# 14_-_JLINK_Debugger.net
KiCad netlist of a schematic drawn in Altium Designer
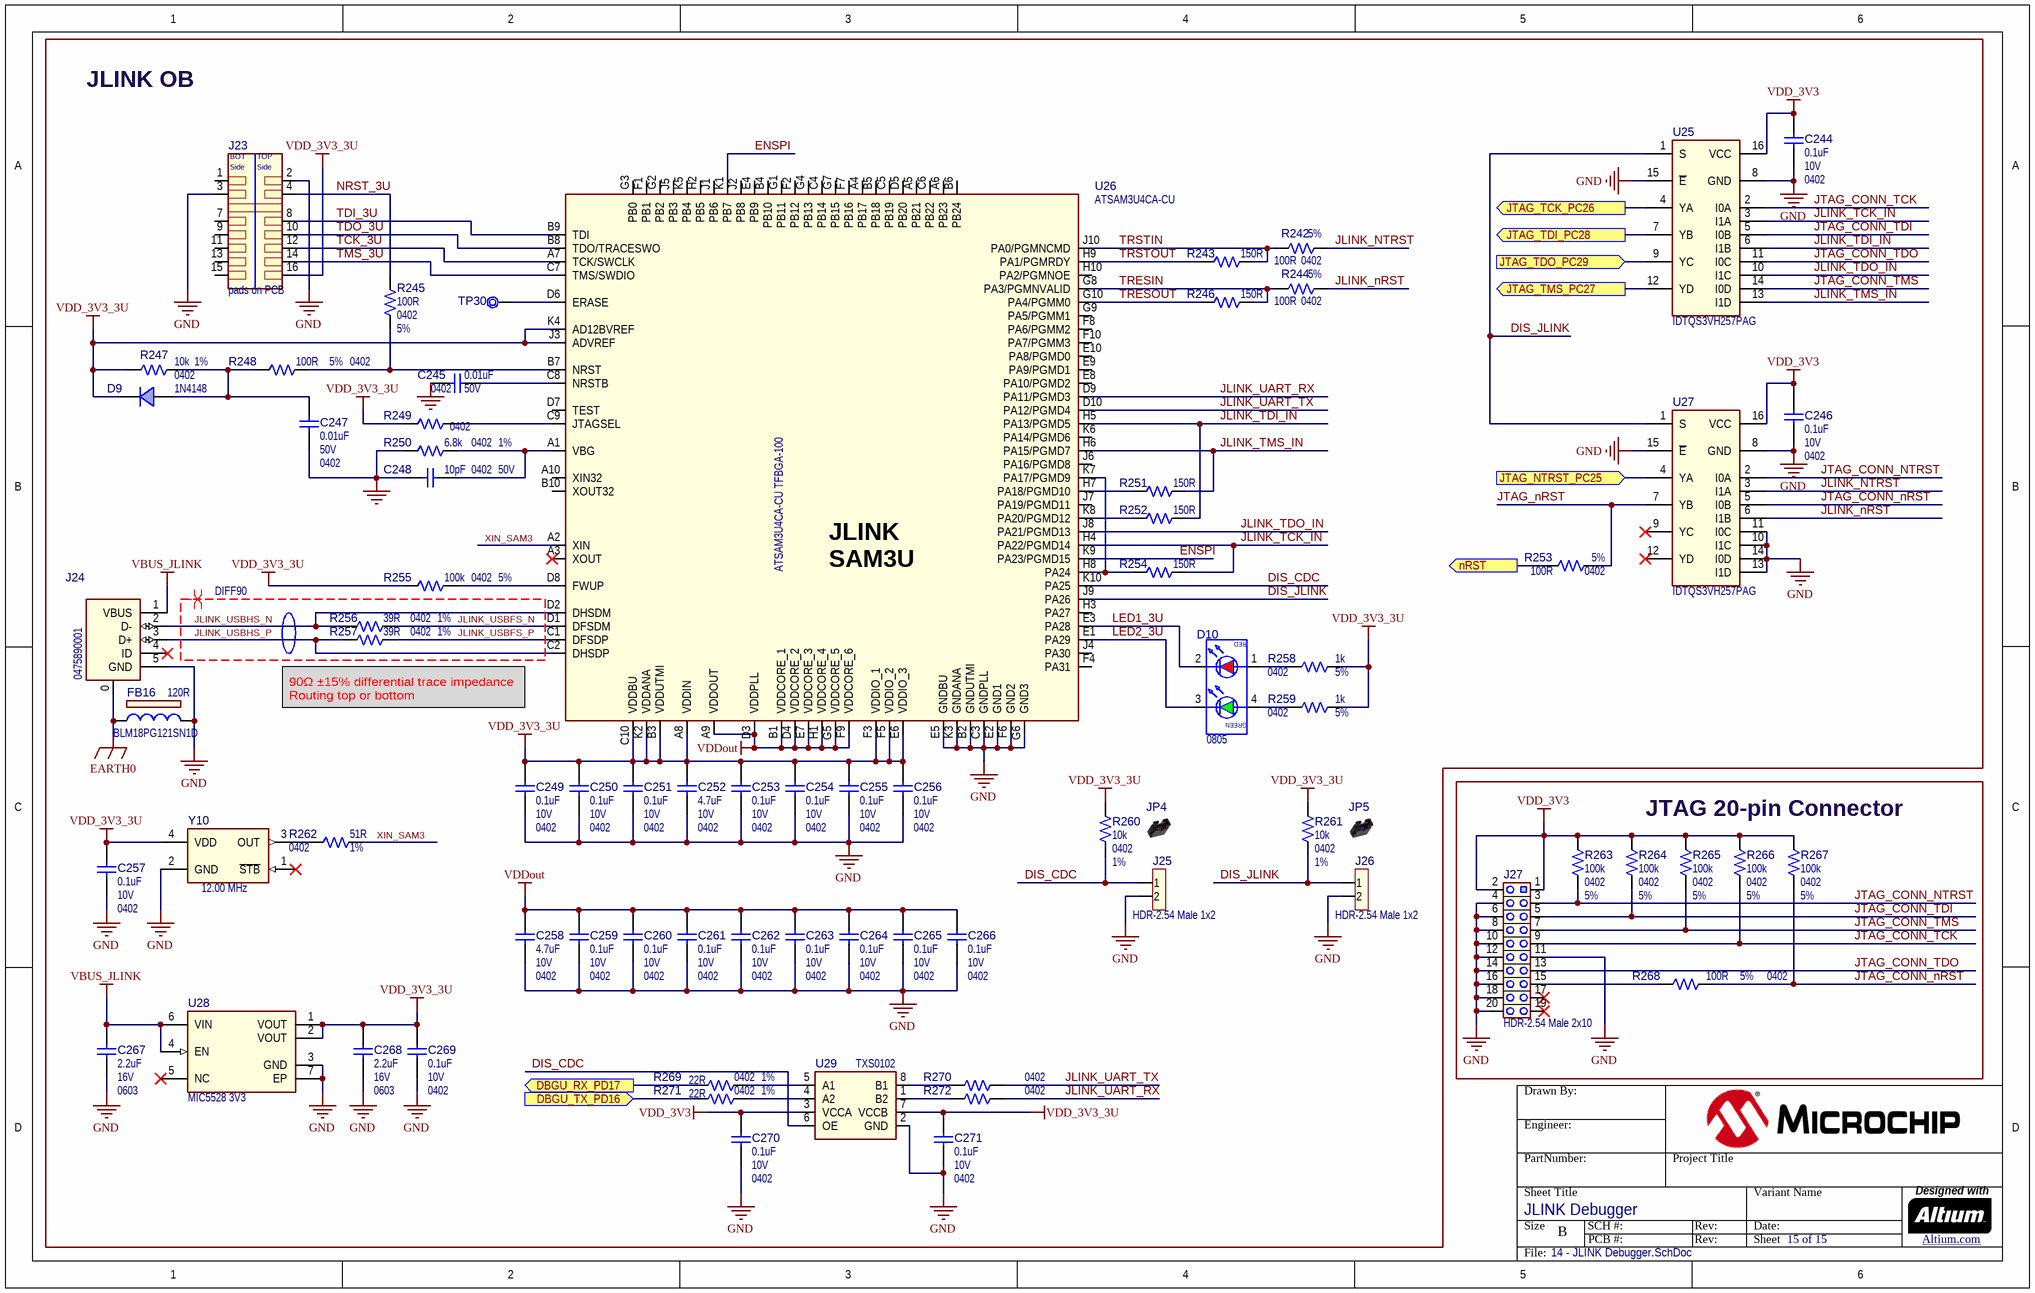
[diagram p0: 14 - JLINK Debugger.SchDoc]

(export (version "E")
  (design (tool "Eeschema 10.0.6"))
  (components
    (comp (ref "C244")
      (value "0.1uF")
      (footprint "CAP_C_0402")
      (description "Capacitor")
      (fields
        (field (name "VOLTAGE") "10V")
        (field (name "PACKAGE") "0402")
        (field (name "TOLERANCE") "10%")
        (field (name "Comment") "Capacitor NP")
      )
      (libsource (lib "MCHP-CDB") (part "Capacitor NP"))
    )
    (comp (ref "C245")
      (value "0.01uF")
      (footprint "CAP_C_0402")
      (description "Capacitor")
      (fields
        (field (name "VOLTAGE") "50V")
        (field (name "PACKAGE") "0402")
        (field (name "TOLERANCE") "10%")
        (field (name "Comment") "Capacitor NP")
      )
      (libsource (lib "MCHP-CDB") (part "Capacitor NP"))
    )
    (comp (ref "C246")
      (value "0.1uF")
      (footprint "CAP_C_0402")
      (description "Capacitor")
      (fields
        (field (name "VOLTAGE") "10V")
        (field (name "PACKAGE") "0402")
        (field (name "TOLERANCE") "10%")
        (field (name "Comment") "Capacitor NP")
      )
      (libsource (lib "MCHP-CDB") (part "Capacitor NP"))
    )
    (comp (ref "C247")
      (value "0.01uF")
      (footprint "CAP_C_0402")
      (description "Capacitor")
      (fields
        (field (name "VOLTAGE") "50V")
        (field (name "PACKAGE") "0402")
        (field (name "TOLERANCE") "10%")
        (field (name "Comment") "Capacitor NP")
      )
      (libsource (lib "MCHP-CDB") (part "Capacitor NP"))
    )
    (comp (ref "C248")
      (value "10pF")
      (footprint "CAP_C_0402")
      (fields
        (field (name "VOLTAGE") "50V")
        (field (name "PACKAGE") "0402")
        (field (name "TOLERANCE") "5%")
        (field (name "Comment") "Capacitor NP")
      )
      (libsource (lib "") (part "Capacitor NP_1"))
    )
    (comp (ref "C249")
      (value "0.1uF")
      (footprint "CAP_C_0402")
      (description "Capacitor")
      (fields
        (field (name "VOLTAGE") "10V")
        (field (name "PACKAGE") "0402")
        (field (name "TOLERANCE") "10%")
        (field (name "Comment") "Capacitor NP")
      )
      (libsource (lib "MCHP-CDB") (part "Capacitor NP"))
    )
    (comp (ref "C250")
      (value "0.1uF")
      (footprint "CAP_C_0402")
      (description "Capacitor")
      (fields
        (field (name "VOLTAGE") "10V")
        (field (name "PACKAGE") "0402")
        (field (name "TOLERANCE") "10%")
        (field (name "Comment") "Capacitor NP")
      )
      (libsource (lib "MCHP-CDB") (part "Capacitor NP"))
    )
    (comp (ref "C251")
      (value "0.1uF")
      (footprint "CAP_C_0402")
      (description "Capacitor")
      (fields
        (field (name "VOLTAGE") "10V")
        (field (name "PACKAGE") "0402")
        (field (name "TOLERANCE") "10%")
        (field (name "Comment") "Capacitor NP")
      )
      (libsource (lib "MCHP-CDB") (part "Capacitor NP"))
    )
    (comp (ref "C252")
      (value "4.7uF")
      (footprint "CAP_C_0402")
      (description "Capacitor")
      (fields
        (field (name "VOLTAGE") "10V")
        (field (name "PACKAGE") "0402")
        (field (name "TOLERANCE") "10%")
        (field (name "Comment") "Capacitor NP")
      )
      (libsource (lib "MCHP-CDB") (part "Capacitor NP"))
    )
    (comp (ref "C253")
      (value "0.1uF")
      (footprint "CAP_C_0402")
      (description "Capacitor")
      (fields
        (field (name "VOLTAGE") "10V")
        (field (name "PACKAGE") "0402")
        (field (name "TOLERANCE") "10%")
        (field (name "Comment") "Capacitor NP")
      )
      (libsource (lib "MCHP-CDB") (part "Capacitor NP"))
    )
    (comp (ref "C254")
      (value "0.1uF")
      (footprint "CAP_C_0402")
      (description "Capacitor")
      (fields
        (field (name "VOLTAGE") "10V")
        (field (name "PACKAGE") "0402")
        (field (name "TOLERANCE") "10%")
        (field (name "Comment") "Capacitor NP")
      )
      (libsource (lib "MCHP-CDB") (part "Capacitor NP"))
    )
    (comp (ref "C255")
      (value "0.1uF")
      (footprint "CAP_C_0402")
      (description "Capacitor")
      (fields
        (field (name "VOLTAGE") "10V")
        (field (name "PACKAGE") "0402")
        (field (name "TOLERANCE") "10%")
        (field (name "Comment") "Capacitor NP")
      )
      (libsource (lib "MCHP-CDB") (part "Capacitor NP"))
    )
    (comp (ref "C256")
      (value "0.1uF")
      (footprint "CAP_C_0402")
      (description "Capacitor")
      (fields
        (field (name "VOLTAGE") "10V")
        (field (name "PACKAGE") "0402")
        (field (name "TOLERANCE") "10%")
        (field (name "Comment") "Capacitor NP")
      )
      (libsource (lib "MCHP-CDB") (part "Capacitor NP"))
    )
    (comp (ref "C257")
      (value "0.1uF")
      (footprint "CAP_C_0402")
      (description "Capacitor")
      (fields
        (field (name "VOLTAGE") "10V")
        (field (name "PACKAGE") "0402")
        (field (name "TOLERANCE") "10%")
        (field (name "Comment") "Capacitor NP")
      )
      (libsource (lib "MCHP-CDB") (part "Capacitor NP"))
    )
    (comp (ref "C258")
      (value "4.7uF")
      (footprint "CAP_C_0402")
      (description "Capacitor")
      (fields
        (field (name "VOLTAGE") "10V")
        (field (name "PACKAGE") "0402")
        (field (name "TOLERANCE") "10%")
        (field (name "Comment") "Capacitor NP")
      )
      (libsource (lib "MCHP-CDB") (part "Capacitor NP"))
    )
    (comp (ref "C259")
      (value "0.1uF")
      (footprint "CAP_C_0402")
      (description "Capacitor")
      (fields
        (field (name "VOLTAGE") "10V")
        (field (name "PACKAGE") "0402")
        (field (name "TOLERANCE") "10%")
        (field (name "Comment") "Capacitor NP")
      )
      (libsource (lib "MCHP-CDB") (part "Capacitor NP"))
    )
    (comp (ref "C260")
      (value "0.1uF")
      (footprint "CAP_C_0402")
      (description "Capacitor")
      (fields
        (field (name "VOLTAGE") "10V")
        (field (name "PACKAGE") "0402")
        (field (name "TOLERANCE") "10%")
        (field (name "Comment") "Capacitor NP")
      )
      (libsource (lib "MCHP-CDB") (part "Capacitor NP"))
    )
    (comp (ref "C261")
      (value "0.1uF")
      (footprint "CAP_C_0402")
      (description "Capacitor")
      (fields
        (field (name "VOLTAGE") "10V")
        (field (name "PACKAGE") "0402")
        (field (name "TOLERANCE") "10%")
        (field (name "Comment") "Capacitor NP")
      )
      (libsource (lib "MCHP-CDB") (part "Capacitor NP"))
    )
    (comp (ref "C262")
      (value "0.1uF")
      (footprint "CAP_C_0402")
      (description "Capacitor")
      (fields
        (field (name "VOLTAGE") "10V")
        (field (name "PACKAGE") "0402")
        (field (name "TOLERANCE") "10%")
        (field (name "Comment") "Capacitor NP")
      )
      (libsource (lib "MCHP-CDB") (part "Capacitor NP"))
    )
    (comp (ref "C263")
      (value "0.1uF")
      (footprint "CAP_C_0402")
      (description "Capacitor")
      (fields
        (field (name "VOLTAGE") "10V")
        (field (name "PACKAGE") "0402")
        (field (name "TOLERANCE") "10%")
        (field (name "Comment") "Capacitor NP")
      )
      (libsource (lib "MCHP-CDB") (part "Capacitor NP"))
    )
    (comp (ref "C264")
      (value "0.1uF")
      (footprint "CAP_C_0402")
      (description "Capacitor")
      (fields
        (field (name "VOLTAGE") "10V")
        (field (name "PACKAGE") "0402")
        (field (name "TOLERANCE") "10%")
        (field (name "Comment") "Capacitor NP")
      )
      (libsource (lib "MCHP-CDB") (part "Capacitor NP"))
    )
    (comp (ref "C265")
      (value "0.1uF")
      (footprint "CAP_C_0402")
      (description "Capacitor")
      (fields
        (field (name "VOLTAGE") "10V")
        (field (name "PACKAGE") "0402")
        (field (name "TOLERANCE") "10%")
        (field (name "Comment") "Capacitor NP")
      )
      (libsource (lib "MCHP-CDB") (part "Capacitor NP"))
    )
    (comp (ref "C266")
      (value "0.1uF")
      (footprint "CAP_C_0402")
      (description "Capacitor")
      (fields
        (field (name "VOLTAGE") "10V")
        (field (name "PACKAGE") "0402")
        (field (name "TOLERANCE") "10%")
        (field (name "Comment") "Capacitor NP")
      )
      (libsource (lib "MCHP-CDB") (part "Capacitor NP"))
    )
    (comp (ref "C267")
      (value "2.2uF")
      (footprint "CAP_C_0603")
      (description "Capacitor")
      (fields
        (field (name "VOLTAGE") "16V")
        (field (name "PACKAGE") "0603")
        (field (name "TOLERANCE") "10%")
        (field (name "Comment") "Capacitor NP")
      )
      (libsource (lib "MCHP-CDB") (part "Capacitor NP"))
    )
    (comp (ref "C268")
      (value "2.2uF")
      (footprint "CAP_C_0603")
      (description "Capacitor")
      (fields
        (field (name "VOLTAGE") "16V")
        (field (name "PACKAGE") "0603")
        (field (name "TOLERANCE") "10%")
        (field (name "Comment") "Capacitor NP")
      )
      (libsource (lib "MCHP-CDB") (part "Capacitor NP"))
    )
    (comp (ref "C269")
      (value "0.1uF")
      (footprint "CAP_C_0402")
      (description "Capacitor")
      (fields
        (field (name "VOLTAGE") "10V")
        (field (name "PACKAGE") "0402")
        (field (name "TOLERANCE") "10%")
        (field (name "Comment") "Capacitor NP")
      )
      (libsource (lib "MCHP-CDB") (part "Capacitor NP"))
    )
    (comp (ref "C270")
      (value "0.1uF")
      (footprint "CAP_C_0402")
      (description "Capacitor")
      (fields
        (field (name "VOLTAGE") "10V")
        (field (name "PACKAGE") "0402")
        (field (name "TOLERANCE") "10%")
        (field (name "Comment") "Capacitor NP")
      )
      (libsource (lib "MCHP-CDB") (part "Capacitor NP"))
    )
    (comp (ref "C271")
      (value "0.1uF")
      (footprint "CAP_C_0402")
      (description "Capacitor")
      (fields
        (field (name "VOLTAGE") "10V")
        (field (name "PACKAGE") "0402")
        (field (name "TOLERANCE") "10%")
        (field (name "Comment") "Capacitor NP")
      )
      (libsource (lib "MCHP-CDB") (part "Capacitor NP"))
    )
    (comp (ref "D9")
      (value "1N4148")
      (footprint "SOD-323")
      (description "DIO RECT 1N4148 855mV 300mA 75V SOD-323")
      (fields (field (name "POWER") "200mW") (field (name "Comment") "Diode Single"))
      (libsource (lib "MCHP-CDB") (part "Diode Single"))
    )
    (comp (ref "D10")
      (value "LED DUAL 4 pin")
      (footprint "LED_DUAL_SMD_2x1.25mm")
      (description "LED")
      (fields (field (name "PACKAGE") "0805") (field (name "POWER") "75mW"))
      (libsource (lib "MCHP-CDB") (part "LED DUAL 4 pin"))
    )
    (comp (ref "FB16")
      (value "120R")
      (footprint "IND_C_0603")
      (fields
        (field (name "MANUFACTURER PART NUMBER 1") "BLM18PG121SN1D")
        (field (name "Comment") "Ferrite Bead")
      )
      (libsource (lib "MCHP-CDB") (part "Ferrite Bead"))
    )
    (comp (ref "J23")
      (value "pads on PCB")
      (footprint "CON_EDGE-CARD_PCB_RA_MEC1-108-02-F-D-RA1-SL")
      (description "CON_PCB_MEC1-108-02-F-D-RA1-SL")
      (libsource (lib "MCHP-CDB") (part "CON_PCB_MEC1-108-02-F-D-RA1-SL"))
    )
    (comp (ref "J24")
      (value "0475890001")
      (footprint "CON_USB_Micro-AB_SMD_RA_MOLEX_0475890001")
      (fields (field (name "VOLTAGE") "30VAC") (field (name "Comment") "CON USB2.0 Mini_Micro"))
      (libsource (lib "MCHP-CDB") (part "CON USB2.0 Mini_Micro"))
    )
    (comp (ref "J25")
      (value "HDR-2.54 Male 1x2")
      (footprint "HDR_M_2.54_1x2")
      (fields (field (name "Comment") "Header 1x2"))
      (libsource (lib "MCHP-CDB") (part "Header 1x2"))
    )
    (comp (ref "J26")
      (value "HDR-2.54 Male 1x2")
      (footprint "HDR_M_2.54_1x2")
      (fields (field (name "Comment") "Header 1x2"))
      (libsource (lib "MCHP-CDB") (part "Header 1x2"))
    )
    (comp (ref "J27")
      (value "HDR-2.54 Male 2x10")
      (footprint "HDR_M_2.54_2X10_S_TH_V_SAM_TST-110-01-G-D")
      (fields (field (name "Comment") "Header 2x10"))
      (libsource (lib "MCHP-CDB") (part "Header 2x10"))
    )
    (comp (ref "JP4")
      (value "Jumper Mechanical")
      (footprint "Jumper_Mechanical")
      (libsource (lib "MCHP-CDB") (part "Jumper Mechanical"))
    )
    (comp (ref "JP5")
      (value "Jumper Mechanical")
      (footprint "Jumper_Mechanical")
      (libsource (lib "MCHP-CDB") (part "Jumper Mechanical"))
    )
    (comp (ref "R242")
      (value "100R")
      (footprint "RES_C_0402")
      (description "Resistor")
      (fields
        (field (name "PACKAGE") "0402")
        (field (name "TOLERANCE") "5%")
        (field (name "VOLTAGE") "50V")
        (field (name "POWER") "1/16W")
      )
      (libsource (lib "MCHP-CDB") (part "Resistor"))
    )
    (comp (ref "R243")
      (value "150R")
      (footprint "RES_C_0402")
      (description "Resistor")
      (libsource (lib "MCHP-CDB") (part "Resistor"))
    )
    (comp (ref "R244")
      (value "100R")
      (footprint "RES_C_0402")
      (description "Resistor")
      (fields
        (field (name "PACKAGE") "0402")
        (field (name "TOLERANCE") "5%")
        (field (name "VOLTAGE") "50V")
        (field (name "POWER") "1/16W")
      )
      (libsource (lib "MCHP-CDB") (part "Resistor"))
    )
    (comp (ref "R245")
      (value "100R")
      (footprint "RES_C_0402")
      (description "Resistor")
      (fields
        (field (name "PACKAGE") "0402")
        (field (name "TOLERANCE") "5%")
        (field (name "VOLTAGE") "50V")
        (field (name "POWER") "1/16W")
      )
      (libsource (lib "MCHP-CDB") (part "Resistor"))
    )
    (comp (ref "R246")
      (value "150R")
      (footprint "RES_C_0402")
      (description "Resistor")
      (libsource (lib "MCHP-CDB") (part "Resistor"))
    )
    (comp (ref "R247")
      (value "10k")
      (footprint "RES_C_0402")
      (description "Resistor")
      (fields
        (field (name "PACKAGE") "0402")
        (field (name "TOLERANCE") "1%")
        (field (name "VOLTAGE") "50V")
        (field (name "POWER") "1/10W")
      )
      (libsource (lib "MCHP-CDB") (part "Resistor"))
    )
    (comp (ref "R248")
      (value "100R")
      (footprint "RES_C_0402")
      (description "Resistor")
      (fields
        (field (name "PACKAGE") "0402")
        (field (name "TOLERANCE") "5%")
        (field (name "VOLTAGE") "50V")
        (field (name "POWER") "1/16W")
      )
      (libsource (lib "MCHP-CDB") (part "Resistor"))
    )
    (comp (ref "R249")
      (value "Resistor")
      (footprint "RES_C_0402")
      (fields (field (name "PACKAGE") "0402") (field (name "POWER") "1/16W") (field (name "VOLTAGE") "50V"))
      (libsource (lib "MCHP-CDB") (part "Resistor"))
    )
    (comp (ref "R250")
      (value "6.8k")
      (footprint "RES_C_0402")
      (description "Resistor")
      (fields
        (field (name "PACKAGE") "0402")
        (field (name "TOLERANCE") "1%")
        (field (name "VOLTAGE") "50V")
        (field (name "POWER") "1/16W")
      )
      (libsource (lib "MCHP-CDB") (part "Resistor"))
    )
    (comp (ref "R251")
      (value "150R")
      (footprint "RES_C_0402")
      (description "Resistor")
      (libsource (lib "MCHP-CDB") (part "Resistor"))
    )
    (comp (ref "R252")
      (value "150R")
      (footprint "RES_C_0402")
      (description "Resistor")
      (libsource (lib "MCHP-CDB") (part "Resistor"))
    )
    (comp (ref "R253")
      (value "100R")
      (footprint "RES_C_0402")
      (description "Resistor")
      (fields
        (field (name "PACKAGE") "0402")
        (field (name "TOLERANCE") "5%")
        (field (name "VOLTAGE") "50V")
        (field (name "POWER") "1/16W")
      )
      (libsource (lib "MCHP-CDB") (part "Resistor"))
    )
    (comp (ref "R254")
      (value "150R")
      (footprint "RES_C_0402")
      (description "Resistor")
      (libsource (lib "MCHP-CDB") (part "Resistor"))
    )
    (comp (ref "R255")
      (value "100k")
      (footprint "RES_C_0402")
      (description "Resistor")
      (fields
        (field (name "PACKAGE") "0402")
        (field (name "TOLERANCE") "5%")
        (field (name "POWER") "1/10W")
        (field (name "VOLTAGE") "50V")
      )
      (libsource (lib "MCHP-CDB") (part "Resistor"))
    )
    (comp (ref "R256")
      (value "39R")
      (footprint "RES_C_0402")
      (description "Resistor")
      (fields
        (field (name "PACKAGE") "0402")
        (field (name "TOLERANCE") "1%")
        (field (name "POWER") "1/16W")
        (field (name "VOLTAGE") "50V")
      )
      (libsource (lib "MCHP-CDB") (part "Resistor"))
    )
    (comp (ref "R257")
      (value "39R")
      (footprint "RES_C_0402")
      (description "Resistor")
      (fields
        (field (name "PACKAGE") "0402")
        (field (name "TOLERANCE") "1%")
        (field (name "POWER") "1/16W")
        (field (name "VOLTAGE") "50V")
      )
      (libsource (lib "MCHP-CDB") (part "Resistor"))
    )
    (comp (ref "R258")
      (value "1k")
      (footprint "RES_C_0402")
      (description "Resistor")
      (fields
        (field (name "PACKAGE") "0402")
        (field (name "TOLERANCE") "5%")
        (field (name "VOLTAGE") "50V")
        (field (name "POWER") "1/16W")
      )
      (libsource (lib "MCHP-CDB") (part "Resistor"))
    )
    (comp (ref "R259")
      (value "1k")
      (footprint "RES_C_0402")
      (description "Resistor")
      (fields
        (field (name "PACKAGE") "0402")
        (field (name "TOLERANCE") "5%")
        (field (name "VOLTAGE") "50V")
        (field (name "POWER") "1/16W")
      )
      (libsource (lib "MCHP-CDB") (part "Resistor"))
    )
    (comp (ref "R260")
      (value "10k")
      (footprint "RES_C_0402")
      (description "Resistor")
      (fields
        (field (name "PACKAGE") "0402")
        (field (name "TOLERANCE") "1%")
        (field (name "VOLTAGE") "50V")
        (field (name "POWER") "1/10W")
      )
      (libsource (lib "MCHP-CDB") (part "Resistor"))
    )
    (comp (ref "R261")
      (value "10k")
      (footprint "RES_C_0402")
      (description "Resistor")
      (fields
        (field (name "PACKAGE") "0402")
        (field (name "TOLERANCE") "1%")
        (field (name "VOLTAGE") "50V")
        (field (name "POWER") "1/10W")
      )
      (libsource (lib "MCHP-CDB") (part "Resistor"))
    )
    (comp (ref "R262")
      (value "51R")
      (footprint "RES_C_0402")
      (description "Resistor")
      (fields
        (field (name "PACKAGE") "0402")
        (field (name "TOLERANCE") "1%")
        (field (name "VOLTAGE") "50V")
        (field (name "POWER") "1/5W")
      )
      (libsource (lib "MCHP-CDB") (part "Resistor"))
    )
    (comp (ref "R263")
      (value "100k")
      (footprint "RES_C_0402")
      (description "Resistor")
      (fields
        (field (name "PACKAGE") "0402")
        (field (name "TOLERANCE") "5%")
        (field (name "POWER") "1/10W")
        (field (name "VOLTAGE") "50V")
      )
      (libsource (lib "MCHP-CDB") (part "Resistor"))
    )
    (comp (ref "R264")
      (value "100k")
      (footprint "RES_C_0402")
      (description "Resistor")
      (fields
        (field (name "PACKAGE") "0402")
        (field (name "TOLERANCE") "5%")
        (field (name "POWER") "1/10W")
        (field (name "VOLTAGE") "50V")
      )
      (libsource (lib "MCHP-CDB") (part "Resistor"))
    )
    (comp (ref "R265")
      (value "100k")
      (footprint "RES_C_0402")
      (description "Resistor")
      (fields
        (field (name "PACKAGE") "0402")
        (field (name "TOLERANCE") "5%")
        (field (name "POWER") "1/10W")
        (field (name "VOLTAGE") "50V")
      )
      (libsource (lib "MCHP-CDB") (part "Resistor"))
    )
    (comp (ref "R266")
      (value "100k")
      (footprint "RES_C_0402")
      (description "Resistor")
      (fields
        (field (name "PACKAGE") "0402")
        (field (name "TOLERANCE") "5%")
        (field (name "POWER") "1/10W")
        (field (name "VOLTAGE") "50V")
      )
      (libsource (lib "MCHP-CDB") (part "Resistor"))
    )
    (comp (ref "R267")
      (value "100k")
      (footprint "RES_C_0402")
      (description "Resistor")
      (fields
        (field (name "PACKAGE") "0402")
        (field (name "TOLERANCE") "5%")
        (field (name "POWER") "1/10W")
        (field (name "VOLTAGE") "50V")
      )
      (libsource (lib "MCHP-CDB") (part "Resistor"))
    )
    (comp (ref "R268")
      (value "100R")
      (footprint "RES_C_0402")
      (description "Resistor")
      (fields
        (field (name "PACKAGE") "0402")
        (field (name "TOLERANCE") "5%")
        (field (name "VOLTAGE") "50V")
        (field (name "POWER") "1/16W")
      )
      (libsource (lib "MCHP-CDB") (part "Resistor"))
    )
    (comp (ref "R269")
      (value "22R")
      (footprint "RES_C_0402")
      (description "Resistor")
      (fields (field (name "PACKAGE") "0402") (field (name "TOLERANCE") "1%") (field (name "POWER") "1/10W"))
      (libsource (lib "MCHP-CDB") (part "Resistor"))
    )
    (comp (ref "R270")
      (value "Resistor")
      (footprint "RES_C_0402")
      (fields (field (name "PACKAGE") "0402") (field (name "POWER") "1/16W") (field (name "VOLTAGE") "50V"))
      (libsource (lib "MCHP-CDB") (part "Resistor"))
    )
    (comp (ref "R271")
      (value "22R")
      (footprint "RES_C_0402")
      (description "Resistor")
      (fields (field (name "PACKAGE") "0402") (field (name "TOLERANCE") "1%") (field (name "POWER") "1/10W"))
      (libsource (lib "MCHP-CDB") (part "Resistor"))
    )
    (comp (ref "R272")
      (value "Resistor")
      (footprint "RES_C_0402")
      (fields (field (name "PACKAGE") "0402") (field (name "POWER") "1/16W") (field (name "VOLTAGE") "50V"))
      (libsource (lib "MCHP-CDB") (part "Resistor"))
    )
    (comp (ref "TP30")
      (value "Test Point No BOM")
      (footprint "TP_1mm_SMD")
      (description "Test Point")
      (libsource (lib "MCHP-CDB") (part "Test Point No BOM"))
    )
    (comp (ref "U25")
      (value "IDTQS3VH257PAG")
      (footprint "TSSOP-16")
      (fields (field (name "Comment") "IDTQS3VH257 TSSOP-16"))
      (libsource (lib "MCHP-CDB") (part "IDTQS3VH257 TSSOP-16"))
    )
    (comp (ref "U26")
      (value "ATSAM3U4CA-CU TFBGA-100")
      (footprint "TFBGA-100_P0.8_9x9x1.1")
      (fields (field (name "ALTIUM_VALUE") "ATSAM3U4CA-CU"))
      (libsource (lib "MCHP-CDB") (part "ATSAM3U4CA-CU TFBGA-100"))
    )
    (comp (ref "U27")
      (value "IDTQS3VH257PAG")
      (footprint "TSSOP-16")
      (fields (field (name "Comment") "IDTQS3VH257 TSSOP-16"))
      (libsource (lib "MCHP-CDB") (part "IDTQS3VH257 TSSOP-16"))
    )
    (comp (ref "U28")
      (value "MIC5528 3V3")
      (footprint "DFN-6_1.2x1.2")
      (fields (field (name "Comment") "MIC5528MT DFN-6"))
      (libsource (lib "MCHP-CDB") (part "MIC5528MT DFN-6"))
    )
    (comp (ref "U29")
      (value "TXS0102")
      (footprint "US-8")
      (description "Level Shifter")
      (libsource (lib "MCHP-CDB") (part "TXS0102"))
    )
    (comp (ref "Y10")
      (value "12.00 MHz")
      (footprint "OSCILLATOR_DSC60000L2.5W2.0H0.89")
      (fields (field (name "Comment") "OSCILLATOR DSC60XX"))
      (libsource (lib "MCHP-CDB") (part "OSCILLATOR DSC60XX"))
    )
  )
  (nets
    (net (code "1") (name "/DBGU_RX_PD17") (class "Default")
      (node (ref "R269") (pin "1") (pinfunction "1_1") (pintype "passive"))
    )
    (net (code "2") (name "/DBGU_TX_PD16") (class "Default")
      (node (ref "R271") (pin "1") (pinfunction "1_1") (pintype "passive"))
    )
    (net (code "3") (name "/DIS_CDC") (class "Default")
      (node (ref "J25") (pin "1") (pinfunction "1_1") (pintype "passive"))
      (node (ref "R260") (pin "2") (pinfunction "2_2") (pintype "passive"))
      (node (ref "U26") (pin "K10") (pinfunction "PA25_K10") (pintype "passive"))
      (node (ref "U29") (pin "6") (pinfunction "OE_6") (pintype "passive"))
    )
    (net (code "4") (name "/DIS_JLINK") (class "Default")
      (node (ref "J26") (pin "1") (pinfunction "1_1") (pintype "passive"))
      (node (ref "R261") (pin "2") (pinfunction "2_2") (pintype "passive"))
      (node (ref "U25") (pin "1") (pinfunction "S_1") (pintype "passive"))
      (node (ref "U26") (pin "J9") (pinfunction "PA26_J9") (pintype "passive"))
      (node (ref "U27") (pin "1") (pinfunction "S_1") (pintype "passive"))
    )
    (net (code "5") (name "/ENSPI") (class "Default")
      (node (ref "U26") (pin "K1") (pinfunction "PB7_K1") (pintype "passive"))
      (node (ref "U26") (pin "K9") (pinfunction "PA23/PGMD15_K9") (pintype "passive"))
    )
    (net (code "6") (name "/JLINK_NTRST") (class "Default")
      (node (ref "R242") (pin "2") (pinfunction "2_2") (pintype "passive"))
      (node (ref "U27") (pin "3") (pinfunction "I1A_3") (pintype "passive"))
    )
    (net (code "7") (name "/JLINK_TCK_IN") (class "Default")
      (node (ref "R254") (pin "2") (pinfunction "2_2") (pintype "passive"))
      (node (ref "U25") (pin "3") (pinfunction "I1A_3") (pintype "passive"))
      (node (ref "U26") (pin "H4") (pinfunction "PA22/PGMD14_H4") (pintype "passive"))
    )
    (net (code "8") (name "/JLINK_TDI_IN") (class "Default")
      (node (ref "R252") (pin "2") (pinfunction "2_2") (pintype "passive"))
      (node (ref "U25") (pin "6") (pinfunction "I1B_6") (pintype "passive"))
      (node (ref "U26") (pin "H5") (pinfunction "PA13/PGMD5_H5") (pintype "passive"))
    )
    (net (code "9") (name "/JLINK_TDO_IN") (class "Default")
      (node (ref "U25") (pin "10") (pinfunction "I1C_10") (pintype "passive"))
      (node (ref "U26") (pin "J8") (pinfunction "PA21/PGMD13_J8") (pintype "passive"))
    )
    (net (code "10") (name "/JLINK_TMS_IN") (class "Default")
      (node (ref "R251") (pin "2") (pinfunction "2_2") (pintype "passive"))
      (node (ref "U25") (pin "13") (pinfunction "I1D_13") (pintype "passive"))
      (node (ref "U26") (pin "H6") (pinfunction "PA15/PGMD7_H6") (pintype "passive"))
    )
    (net (code "11") (name "/JLINK_UART_RX") (class "Default")
      (node (ref "R272") (pin "2") (pinfunction "2_2") (pintype "passive"))
      (node (ref "U26") (pin "D9") (pinfunction "PA11/PGMD3_D9") (pintype "passive"))
    )
    (net (code "12") (name "/JLINK_UART_TX") (class "Default")
      (node (ref "R270") (pin "2") (pinfunction "2_2") (pintype "passive"))
      (node (ref "U26") (pin "D10") (pinfunction "PA12/PGMD4_D10") (pintype "passive"))
    )
    (net (code "13") (name "/JLINK_USBFS_N") (class "Default")
      (node (ref "R256") (pin "2") (pinfunction "2_2") (pintype "passive"))
      (node (ref "U26") (pin "D1") (pinfunction "DFSDM_D1") (pintype "passive"))
    )
    (net (code "14") (name "/JLINK_USBFS_P") (class "Default")
      (node (ref "R257") (pin "2") (pinfunction "2_2") (pintype "passive"))
      (node (ref "U26") (pin "C1") (pinfunction "DFSDP_C1") (pintype "passive"))
    )
    (net (code "15") (name "/JLINK_USBHS_N") (class "Default")
      (node (ref "J24") (pin "2") (pinfunction "D-_2") (pintype "bidirectional"))
      (node (ref "R256") (pin "1") (pinfunction "1_1") (pintype "passive"))
      (node (ref "U26") (pin "D2") (pinfunction "DHSDM_D2") (pintype "passive"))
    )
    (net (code "16") (name "/JLINK_USBHS_P") (class "Default")
      (node (ref "J24") (pin "3") (pinfunction "D+_3") (pintype "bidirectional"))
      (node (ref "R257") (pin "1") (pinfunction "1_1") (pintype "passive"))
      (node (ref "U26") (pin "C2") (pinfunction "DHSDP_C2") (pintype "passive"))
    )
    (net (code "17") (name "/JLINK_nRST") (class "Default")
      (node (ref "R244") (pin "2") (pinfunction "2_2") (pintype "passive"))
      (node (ref "U27") (pin "6") (pinfunction "I1B_6") (pintype "passive"))
    )
    (net (code "18") (name "/JTAG_CONN_NTRST") (class "Default")
      (node (ref "J27") (pin "3") (pinfunction "3_3") (pintype "passive"))
      (node (ref "R263") (pin "1") (pinfunction "1_1") (pintype "passive"))
      (node (ref "U27") (pin "2") (pinfunction "I0A_2") (pintype "passive"))
    )
    (net (code "19") (name "/JTAG_CONN_TCK") (class "Default")
      (node (ref "J27") (pin "9") (pinfunction "9_9") (pintype "passive"))
      (node (ref "R266") (pin "2") (pinfunction "2_2") (pintype "passive"))
      (node (ref "U25") (pin "2") (pinfunction "I0A_2") (pintype "passive"))
    )
    (net (code "20") (name "/JTAG_CONN_TDI") (class "Default")
      (node (ref "J27") (pin "5") (pinfunction "5_5") (pintype "passive"))
      (node (ref "R264") (pin "1") (pinfunction "1_1") (pintype "passive"))
      (node (ref "U25") (pin "5") (pinfunction "I0B_5") (pintype "passive"))
    )
    (net (code "21") (name "/JTAG_CONN_TDO") (class "Default")
      (node (ref "J27") (pin "13") (pinfunction "13_13") (pintype "passive"))
      (node (ref "U25") (pin "11") (pinfunction "I0C_11") (pintype "passive"))
    )
    (net (code "22") (name "/JTAG_CONN_TMS") (class "Default")
      (node (ref "J27") (pin "7") (pinfunction "7_7") (pintype "passive"))
      (node (ref "R265") (pin "1") (pinfunction "1_1") (pintype "passive"))
      (node (ref "U25") (pin "14") (pinfunction "I0D_14") (pintype "passive"))
    )
    (net (code "23") (name "/JTAG_CONN_nRST") (class "Default")
      (node (ref "R267") (pin "1") (pinfunction "1_1") (pintype "passive"))
      (node (ref "R268") (pin "1") (pinfunction "1_1") (pintype "passive"))
      (node (ref "U27") (pin "5") (pinfunction "I0B_5") (pintype "passive"))
    )
    (net (code "24") (name "/JTAG_NTRST_PC25") (class "Default")
      (node (ref "U27") (pin "4") (pinfunction "YA_4") (pintype "passive"))
    )
    (net (code "25") (name "/JTAG_TCK_PC26") (class "Default")
      (node (ref "U25") (pin "4") (pinfunction "YA_4") (pintype "passive"))
    )
    (net (code "26") (name "/JTAG_TDI_PC28") (class "Default")
      (node (ref "U25") (pin "7") (pinfunction "YB_7") (pintype "passive"))
    )
    (net (code "27") (name "/JTAG_TDO_PC29") (class "Default")
      (node (ref "U25") (pin "9") (pinfunction "YC_9") (pintype "passive"))
    )
    (net (code "28") (name "/JTAG_TMS_PC27") (class "Default")
      (node (ref "U25") (pin "12") (pinfunction "YD_12") (pintype "passive"))
    )
    (net (code "29") (name "/JTAG_nRST") (class "Default")
      (node (ref "R253") (pin "2") (pinfunction "2_2") (pintype "passive"))
      (node (ref "U27") (pin "7") (pinfunction "YB_7") (pintype "passive"))
    )
    (net (code "30") (name "/LED1_3U") (class "Default")
      (node (ref "D10") (pin "2") (pinfunction "K1_2") (pintype "passive"))
      (node (ref "U26") (pin "E3") (pinfunction "PA28_E3") (pintype "passive"))
    )
    (net (code "31") (name "/LED2_3U") (class "Default")
      (node (ref "D10") (pin "3") (pinfunction "K2_3") (pintype "passive"))
      (node (ref "U26") (pin "E1") (pinfunction "PA29_E1") (pintype "passive"))
    )
    (net (code "32") (name "/NRST_3U") (class "Default")
      (node (ref "J23") (pin "4") (pinfunction "4_4") (pintype "passive"))
      (node (ref "R245") (pin "2") (pinfunction "2_2") (pintype "passive"))
    )
    (net (code "33") (name "/TCK_3U") (class "Default")
      (node (ref "J23") (pin "12") (pinfunction "12_12") (pintype "passive"))
      (node (ref "U26") (pin "A7") (pinfunction "TCK/SWCLK_A7") (pintype "passive"))
    )
    (net (code "34") (name "/TDI_3U") (class "Default")
      (node (ref "J23") (pin "8") (pinfunction "8_8") (pintype "passive"))
      (node (ref "U26") (pin "B9") (pinfunction "TDI_B9") (pintype "passive"))
    )
    (net (code "35") (name "/TDO_3U") (class "Default")
      (node (ref "J23") (pin "10") (pinfunction "10_10") (pintype "passive"))
      (node (ref "U26") (pin "B8") (pinfunction "TDO/TRACESWO_B8") (pintype "passive"))
    )
    (net (code "36") (name "/TMS_3U") (class "Default")
      (node (ref "J23") (pin "14") (pinfunction "14_14") (pintype "passive"))
      (node (ref "U26") (pin "C7") (pinfunction "TMS/SWDIO_C7") (pintype "passive"))
    )
    (net (code "37") (name "/TRESIN") (class "Default")
      (node (ref "R244") (pin "1") (pinfunction "1_1") (pintype "passive"))
      (node (ref "R246") (pin "2") (pinfunction "2_2") (pintype "passive"))
      (node (ref "U26") (pin "G8") (pinfunction "PA3/PGMNVALID_G8") (pintype "passive"))
    )
    (net (code "38") (name "/TRESOUT") (class "Default")
      (node (ref "R246") (pin "1") (pinfunction "1_1") (pintype "passive"))
      (node (ref "U26") (pin "G10") (pinfunction "PA4/PGMM0_G10") (pintype "passive"))
    )
    (net (code "39") (name "/TRSTIN") (class "Default")
      (node (ref "R242") (pin "1") (pinfunction "1_1") (pintype "passive"))
      (node (ref "R243") (pin "2") (pinfunction "2_2") (pintype "passive"))
      (node (ref "U26") (pin "J10") (pinfunction "PA0/PGMNCMD_J10") (pintype "passive"))
    )
    (net (code "40") (name "/TRSTOUT") (class "Default")
      (node (ref "R243") (pin "1") (pinfunction "1_1") (pintype "passive"))
      (node (ref "U26") (pin "H9") (pinfunction "PA1/PGMRDY_H9") (pintype "passive"))
    )
    (net (code "41") (name "/XIN_SAM3") (class "Default")
      (node (ref "R262") (pin "2") (pinfunction "2_2") (pintype "passive"))
      (node (ref "U26") (pin "A2") (pinfunction "XIN_A2") (pintype "passive"))
    )
    (net (code "42") (name "/nRST") (class "Default")
      (node (ref "R253") (pin "1") (pinfunction "1_1") (pintype "passive"))
    )
    (net (code "43") (name "EARTH0") (class "Default")
      (node (ref "FB16") (pin "1") (pinfunction "1_1") (pintype "passive"))
      (node (ref "J24") (pin "0") (pinfunction "SHLD_0") (pintype "passive"))
    )
    (net (code "44") (name "GND") (class "Default")
      (node (ref "C244") (pin "2") (pinfunction "2_2") (pintype "passive"))
      (node (ref "C245") (pin "1") (pinfunction "1_1") (pintype "passive"))
      (node (ref "C246") (pin "2") (pinfunction "2_2") (pintype "passive"))
      (node (ref "C247") (pin "1") (pinfunction "1_1") (pintype "passive"))
      (node (ref "C248") (pin "2") (pinfunction "2_2") (pintype "passive"))
      (node (ref "C249") (pin "2") (pinfunction "2_2") (pintype "passive"))
      (node (ref "C250") (pin "1") (pinfunction "1_1") (pintype "passive"))
      (node (ref "C251") (pin "2") (pinfunction "2_2") (pintype "passive"))
      (node (ref "C252") (pin "1") (pinfunction "1_1") (pintype "passive"))
      (node (ref "C253") (pin "1") (pinfunction "1_1") (pintype "passive"))
      (node (ref "C254") (pin "1") (pinfunction "1_1") (pintype "passive"))
      (node (ref "C255") (pin "1") (pinfunction "1_1") (pintype "passive"))
      (node (ref "C256") (pin "1") (pinfunction "1_1") (pintype "passive"))
      (node (ref "C257") (pin "1") (pinfunction "1_1") (pintype "passive"))
      (node (ref "C258") (pin "1") (pinfunction "1_1") (pintype "passive"))
      (node (ref "C259") (pin "1") (pinfunction "1_1") (pintype "passive"))
      (node (ref "C260") (pin "2") (pinfunction "2_2") (pintype "passive"))
      (node (ref "C261") (pin "2") (pinfunction "2_2") (pintype "passive"))
      (node (ref "C262") (pin "2") (pinfunction "2_2") (pintype "passive"))
      (node (ref "C263") (pin "2") (pinfunction "2_2") (pintype "passive"))
      (node (ref "C264") (pin "2") (pinfunction "2_2") (pintype "passive"))
      (node (ref "C265") (pin "2") (pinfunction "2_2") (pintype "passive"))
      (node (ref "C266") (pin "1") (pinfunction "1_1") (pintype "passive"))
      (node (ref "C267") (pin "2") (pinfunction "2_2") (pintype "passive"))
      (node (ref "C268") (pin "1") (pinfunction "1_1") (pintype "passive"))
      (node (ref "C269") (pin "1") (pinfunction "1_1") (pintype "passive"))
      (node (ref "C270") (pin "1") (pinfunction "1_1") (pintype "passive"))
      (node (ref "C271") (pin "1") (pinfunction "1_1") (pintype "passive"))
      (node (ref "FB16") (pin "2") (pinfunction "2_2") (pintype "passive"))
      (node (ref "J23") (pin "2") (pinfunction "2_2") (pintype "passive"))
      (node (ref "J23") (pin "3") (pinfunction "3_3") (pintype "passive"))
      (node (ref "J24") (pin "5") (pinfunction "GND_5") (pintype "power_in"))
      (node (ref "J25") (pin "2") (pinfunction "2_2") (pintype "passive"))
      (node (ref "J26") (pin "2") (pinfunction "2_2") (pintype "passive"))
      (node (ref "J27") (pin "10") (pinfunction "10_10") (pintype "passive"))
      (node (ref "J27") (pin "11") (pinfunction "11_11") (pintype "passive"))
      (node (ref "J27") (pin "12") (pinfunction "12_12") (pintype "passive"))
      (node (ref "J27") (pin "14") (pinfunction "14_14") (pintype "passive"))
      (node (ref "J27") (pin "16") (pinfunction "16_16") (pintype "passive"))
      (node (ref "J27") (pin "18") (pinfunction "18_18") (pintype "passive"))
      (node (ref "J27") (pin "20") (pinfunction "20_20") (pintype "passive"))
      (node (ref "J27") (pin "4") (pinfunction "4_4") (pintype "passive"))
      (node (ref "J27") (pin "6") (pinfunction "6_6") (pintype "passive"))
      (node (ref "J27") (pin "8") (pinfunction "8_8") (pintype "passive"))
      (node (ref "R250") (pin "1") (pinfunction "1_1") (pintype "passive"))
      (node (ref "U25") (pin "15") (pinfunction "~{E}_15") (pintype "passive"))
      (node (ref "U25") (pin "8") (pinfunction "GND_8") (pintype "passive"))
      (node (ref "U26") (pin "B2") (pinfunction "GNDUTMI_B2") (pintype "passive"))
      (node (ref "U26") (pin "C3") (pinfunction "GNDPLL_C3") (pintype "passive"))
      (node (ref "U26") (pin "E2") (pinfunction "GND1_E2") (pintype "power_in"))
      (node (ref "U26") (pin "E5") (pinfunction "GNDBU_E5") (pintype "passive"))
      (node (ref "U26") (pin "F6") (pinfunction "GND2_F6") (pintype "power_in"))
      (node (ref "U26") (pin "G6") (pinfunction "GND3_G6") (pintype "power_in"))
      (node (ref "U26") (pin "K3") (pinfunction "GNDANA_K3") (pintype "passive"))
      (node (ref "U27") (pin "10") (pinfunction "I1C_10") (pintype "passive"))
      (node (ref "U27") (pin "11") (pinfunction "I0C_11") (pintype "passive"))
      (node (ref "U27") (pin "13") (pinfunction "I1D_13") (pintype "passive"))
      (node (ref "U27") (pin "14") (pinfunction "I0D_14") (pintype "passive"))
      (node (ref "U27") (pin "15") (pinfunction "~{E}_15") (pintype "passive"))
      (node (ref "U27") (pin "8") (pinfunction "GND_8") (pintype "passive"))
      (node (ref "U28") (pin "3") (pinfunction "GND_3") (pintype "power_in"))
      (node (ref "U28") (pin "7") (pinfunction "EP_7") (pintype "power_in"))
      (node (ref "U29") (pin "2") (pinfunction "GND_2") (pintype "passive"))
      (node (ref "Y10") (pin "2") (pinfunction "GND_2") (pintype "power_in"))
    )
    (net (code "45") (name "Net-(D9-A)") (class "Default")
      (node (ref "C247") (pin "2") (pinfunction "2_2") (pintype "passive"))
      (node (ref "D9") (pin "1") (pinfunction "A_1") (pintype "passive"))
      (node (ref "R247") (pin "2") (pinfunction "2_2") (pintype "passive"))
      (node (ref "R248") (pin "1") (pinfunction "1_1") (pintype "passive"))
    )
    (net (code "46") (name "Net-(D10-A1)") (class "Default")
      (node (ref "D10") (pin "1") (pinfunction "A1_1") (pintype "passive"))
      (node (ref "R258") (pin "2") (pinfunction "2_2") (pintype "passive"))
    )
    (net (code "47") (name "Net-(D10-A2)") (class "Default")
      (node (ref "D10") (pin "4") (pinfunction "A2_4") (pintype "passive"))
      (node (ref "R259") (pin "2") (pinfunction "2_2") (pintype "passive"))
    )
    (net (code "48") (name "Net-(J27-Pad15)") (class "Default")
      (node (ref "J27") (pin "15") (pinfunction "15_15") (pintype "passive"))
      (node (ref "R268") (pin "2") (pinfunction "2_2") (pintype "passive"))
    )
    (net (code "49") (name "Net-(U26-ERASE)") (class "Default")
      (node (ref "TP30") (pin "1") (pinfunction "1_1") (pintype "passive"))
      (node (ref "U26") (pin "D6") (pinfunction "ERASE_D6") (pintype "passive"))
    )
    (net (code "50") (name "Net-(U26-FWUP)") (class "Default")
      (node (ref "R255") (pin "2") (pinfunction "2_2") (pintype "passive"))
      (node (ref "U26") (pin "D8") (pinfunction "FWUP_D8") (pintype "passive"))
    )
    (net (code "51") (name "Net-(U26-JTAGSEL)") (class "Default")
      (node (ref "R249") (pin "2") (pinfunction "2_2") (pintype "passive"))
      (node (ref "U26") (pin "C9") (pinfunction "JTAGSEL_C9") (pintype "passive"))
    )
    (net (code "52") (name "Net-(U26-NRST)") (class "Default")
      (node (ref "R245") (pin "1") (pinfunction "1_1") (pintype "passive"))
      (node (ref "R248") (pin "2") (pinfunction "2_2") (pintype "passive"))
      (node (ref "U26") (pin "B7") (pinfunction "NRST_B7") (pintype "passive"))
    )
    (net (code "53") (name "Net-(U26-NRSTB)") (class "Default")
      (node (ref "C245") (pin "2") (pinfunction "2_2") (pintype "passive"))
      (node (ref "U26") (pin "C8") (pinfunction "NRSTB_C8") (pintype "passive"))
    )
    (net (code "54") (name "Net-(U26-PA17{slash}PGMD9)") (class "Default")
      (node (ref "R254") (pin "1") (pinfunction "1_1") (pintype "passive"))
      (node (ref "U26") (pin "H8") (pinfunction "PA24_H8") (pintype "passive"))
      (node (ref "U26") (pin "K7") (pinfunction "PA17/PGMD9_K7") (pintype "passive"))
    )
    (net (code "55") (name "Net-(U26-PA18{slash}PGMD10)") (class "Default")
      (node (ref "R251") (pin "1") (pinfunction "1_1") (pintype "passive"))
      (node (ref "U26") (pin "H7") (pinfunction "PA18/PGMD10_H7") (pintype "passive"))
    )
    (net (code "56") (name "Net-(U26-PA20{slash}PGMD12)") (class "Default")
      (node (ref "R252") (pin "1") (pinfunction "1_1") (pintype "passive"))
      (node (ref "U26") (pin "K8") (pinfunction "PA20/PGMD12_K8") (pintype "passive"))
    )
    (net (code "57") (name "Net-(U26-VBG)") (class "Default")
      (node (ref "C248") (pin "1") (pinfunction "1_1") (pintype "passive"))
      (node (ref "R250") (pin "2") (pinfunction "2_2") (pintype "passive"))
      (node (ref "U26") (pin "A1") (pinfunction "VBG_A1") (pintype "passive"))
    )
    (net (code "58") (name "Net-(U29-A1)") (class "Default")
      (node (ref "R269") (pin "2") (pinfunction "2_2") (pintype "passive"))
      (node (ref "U29") (pin "5") (pinfunction "A1_5") (pintype "passive"))
    )
    (net (code "59") (name "Net-(U29-A2)") (class "Default")
      (node (ref "R271") (pin "2") (pinfunction "2_2") (pintype "passive"))
      (node (ref "U29") (pin "4") (pinfunction "A2_4") (pintype "passive"))
    )
    (net (code "60") (name "Net-(U29-B1)") (class "Default")
      (node (ref "R270") (pin "1") (pinfunction "1_1") (pintype "passive"))
      (node (ref "U29") (pin "8") (pinfunction "B1_8") (pintype "passive"))
    )
    (net (code "61") (name "Net-(U29-B2)") (class "Default")
      (node (ref "R272") (pin "1") (pinfunction "1_1") (pintype "passive"))
      (node (ref "U29") (pin "1") (pinfunction "B2_1") (pintype "passive"))
    )
    (net (code "62") (name "Net-(Y10-OUT)") (class "Default")
      (node (ref "R262") (pin "1") (pinfunction "1_1") (pintype "passive"))
      (node (ref "Y10") (pin "3") (pinfunction "OUT_3") (pintype "output"))
    )
    (net (code "63") (name "VBUS_JLINK") (class "Default")
      (node (ref "C267") (pin "1") (pinfunction "1_1") (pintype "passive"))
      (node (ref "J24") (pin "1") (pinfunction "VBUS_1") (pintype "power_in"))
      (node (ref "U28") (pin "4") (pinfunction "EN_4") (pintype "input"))
      (node (ref "U28") (pin "6") (pinfunction "VIN_6") (pintype "power_in"))
    )
    (net (code "64") (name "VDD_3V3") (class "Default")
      (node (ref "C244") (pin "1") (pinfunction "1_1") (pintype "passive"))
      (node (ref "C246") (pin "1") (pinfunction "1_1") (pintype "passive"))
      (node (ref "C270") (pin "2") (pinfunction "2_2") (pintype "passive"))
      (node (ref "J27") (pin "1") (pinfunction "1_1") (pintype "passive"))
      (node (ref "J27") (pin "2") (pinfunction "2_2") (pintype "passive"))
      (node (ref "R263") (pin "2") (pinfunction "2_2") (pintype "passive"))
      (node (ref "R264") (pin "2") (pinfunction "2_2") (pintype "passive"))
      (node (ref "R265") (pin "2") (pinfunction "2_2") (pintype "passive"))
      (node (ref "R266") (pin "1") (pinfunction "1_1") (pintype "passive"))
      (node (ref "R267") (pin "2") (pinfunction "2_2") (pintype "passive"))
      (node (ref "U25") (pin "16") (pinfunction "VCC_16") (pintype "passive"))
      (node (ref "U27") (pin "16") (pinfunction "VCC_16") (pintype "passive"))
      (node (ref "U29") (pin "3") (pinfunction "VCCA_3") (pintype "passive"))
    )
    (net (code "65") (name "VDD_3V3_3U") (class "Default")
      (node (ref "C249") (pin "1") (pinfunction "1_1") (pintype "passive"))
      (node (ref "C250") (pin "2") (pinfunction "2_2") (pintype "passive"))
      (node (ref "C251") (pin "1") (pinfunction "1_1") (pintype "passive"))
      (node (ref "C252") (pin "2") (pinfunction "2_2") (pintype "passive"))
      (node (ref "C253") (pin "2") (pinfunction "2_2") (pintype "passive"))
      (node (ref "C254") (pin "2") (pinfunction "2_2") (pintype "passive"))
      (node (ref "C255") (pin "2") (pinfunction "2_2") (pintype "passive"))
      (node (ref "C256") (pin "2") (pinfunction "2_2") (pintype "passive"))
      (node (ref "C257") (pin "2") (pinfunction "2_2") (pintype "passive"))
      (node (ref "C268") (pin "2") (pinfunction "2_2") (pintype "passive"))
      (node (ref "C269") (pin "2") (pinfunction "2_2") (pintype "passive"))
      (node (ref "C271") (pin "2") (pinfunction "2_2") (pintype "passive"))
      (node (ref "D9") (pin "2") (pinfunction "K_2") (pintype "passive"))
      (node (ref "J23") (pin "16") (pinfunction "16_16") (pintype "passive"))
      (node (ref "R247") (pin "1") (pinfunction "1_1") (pintype "passive"))
      (node (ref "R249") (pin "1") (pinfunction "1_1") (pintype "passive"))
      (node (ref "R255") (pin "1") (pinfunction "1_1") (pintype "passive"))
      (node (ref "R258") (pin "1") (pinfunction "1_1") (pintype "passive"))
      (node (ref "R259") (pin "1") (pinfunction "1_1") (pintype "passive"))
      (node (ref "R260") (pin "1") (pinfunction "1_1") (pintype "passive"))
      (node (ref "R261") (pin "1") (pinfunction "1_1") (pintype "passive"))
      (node (ref "U26") (pin "A8") (pinfunction "VDDIN_A8") (pintype "passive"))
      (node (ref "U26") (pin "B3") (pinfunction "VDDUTMI_B3") (pintype "passive"))
      (node (ref "U26") (pin "C10") (pinfunction "VDDBU_C10") (pintype "passive"))
      (node (ref "U26") (pin "E6") (pinfunction "VDDIO_3_E6") (pintype "passive"))
      (node (ref "U26") (pin "F3") (pinfunction "VDDIO_1_F3") (pintype "passive"))
      (node (ref "U26") (pin "F5") (pinfunction "VDDIO_2_F5") (pintype "passive"))
      (node (ref "U26") (pin "J3") (pinfunction "ADVREF_J3") (pintype "passive"))
      (node (ref "U26") (pin "K2") (pinfunction "VDDANA_K2") (pintype "passive"))
      (node (ref "U26") (pin "K4") (pinfunction "AD12BVREF_K4") (pintype "passive"))
      (node (ref "U28") (pin "1") (pinfunction "VOUT_1") (pintype "power_in"))
      (node (ref "U28") (pin "2") (pinfunction "VOUT_2") (pintype "power_in"))
      (node (ref "U29") (pin "7") (pinfunction "VCCB_7") (pintype "passive"))
      (node (ref "Y10") (pin "4") (pinfunction "VDD_4") (pintype "power_in"))
    )
    (net (code "66") (name "VDDout") (class "Default")
      (node (ref "C258") (pin "2") (pinfunction "2_2") (pintype "passive"))
      (node (ref "C259") (pin "2") (pinfunction "2_2") (pintype "passive"))
      (node (ref "C260") (pin "1") (pinfunction "1_1") (pintype "passive"))
      (node (ref "C261") (pin "1") (pinfunction "1_1") (pintype "passive"))
      (node (ref "C262") (pin "1") (pinfunction "1_1") (pintype "passive"))
      (node (ref "C263") (pin "1") (pinfunction "1_1") (pintype "passive"))
      (node (ref "C264") (pin "1") (pinfunction "1_1") (pintype "passive"))
      (node (ref "C265") (pin "1") (pinfunction "1_1") (pintype "passive"))
      (node (ref "C266") (pin "2") (pinfunction "2_2") (pintype "passive"))
      (node (ref "U26") (pin "A9") (pinfunction "VDDOUT_A9") (pintype "passive"))
      (node (ref "U26") (pin "B1") (pinfunction "VDDCORE_1_B1") (pintype "passive"))
      (node (ref "U26") (pin "D3") (pinfunction "VDDPLL_D3") (pintype "passive"))
      (node (ref "U26") (pin "D4") (pinfunction "VDDCORE_2_D4") (pintype "passive"))
      (node (ref "U26") (pin "E7") (pinfunction "VDDCORE_3_E7") (pintype "passive"))
      (node (ref "U26") (pin "F9") (pinfunction "VDDCORE_6_F9") (pintype "passive"))
      (node (ref "U26") (pin "G5") (pinfunction "VDDCORE_5_G5") (pintype "passive"))
      (node (ref "U26") (pin "H1") (pinfunction "VDDCORE_4_H1") (pintype "passive"))
    )
    (net (code "67") (name "unconnected-(J23-Pad1)") (class "Default")
      (node (ref "J23") (pin "1") (pinfunction "1_1") (pintype "passive"))
    )
    (net (code "68") (name "unconnected-(J23-Pad7)") (class "Default")
      (node (ref "J23") (pin "7") (pinfunction "7_7") (pintype "passive"))
    )
    (net (code "69") (name "unconnected-(J23-Pad9)") (class "Default")
      (node (ref "J23") (pin "9") (pinfunction "9_9") (pintype "passive"))
    )
    (net (code "70") (name "unconnected-(J23-Pad11)") (class "Default")
      (node (ref "J23") (pin "11") (pinfunction "11_11") (pintype "passive"))
    )
    (net (code "71") (name "unconnected-(J23-Pad13)") (class "Default")
      (node (ref "J23") (pin "13") (pinfunction "13_13") (pintype "passive"))
    )
    (net (code "72") (name "unconnected-(J23-Pad15)") (class "Default")
      (node (ref "J23") (pin "15") (pinfunction "15_15") (pintype "passive"))
    )
    (net (code "73") (name "unconnected-(J24-ID-Pad4)") (class "Default")
      (node (ref "J24") (pin "4") (pinfunction "ID_4") (pintype "passive+no_connect"))
    )
    (net (code "74") (name "unconnected-(J27-Pad17)") (class "Default")
      (node (ref "J27") (pin "17") (pinfunction "17_17") (pintype "passive+no_connect"))
    )
    (net (code "75") (name "unconnected-(J27-Pad19)") (class "Default")
      (node (ref "J27") (pin "19") (pinfunction "19_19") (pintype "passive+no_connect"))
    )
    (net (code "76") (name "unconnected-(U26-PA2{slash}PGMNOE-PadH10)") (class "Default")
      (node (ref "U26") (pin "H10") (pinfunction "PA2/PGMNOE_H10") (pintype "passive"))
    )
    (net (code "77") (name "unconnected-(U26-PA5{slash}PGMM1-PadG9)") (class "Default")
      (node (ref "U26") (pin "G9") (pinfunction "PA5/PGMM1_G9") (pintype "passive"))
    )
    (net (code "78") (name "unconnected-(U26-PA6{slash}PGMM2-PadF8)") (class "Default")
      (node (ref "U26") (pin "F8") (pinfunction "PA6/PGMM2_F8") (pintype "passive"))
    )
    (net (code "79") (name "unconnected-(U26-PA7{slash}PGMM3-PadF10)") (class "Default")
      (node (ref "U26") (pin "F10") (pinfunction "PA7/PGMM3_F10") (pintype "passive"))
    )
    (net (code "80") (name "unconnected-(U26-PA8{slash}PGMD0-PadE10)") (class "Default")
      (node (ref "U26") (pin "E10") (pinfunction "PA8/PGMD0_E10") (pintype "passive"))
    )
    (net (code "81") (name "unconnected-(U26-PA9{slash}PGMD1-PadE9)") (class "Default")
      (node (ref "U26") (pin "E9") (pinfunction "PA9/PGMD1_E9") (pintype "passive"))
    )
    (net (code "82") (name "unconnected-(U26-PA10{slash}PGMD2-PadE8)") (class "Default")
      (node (ref "U26") (pin "E8") (pinfunction "PA10/PGMD2_E8") (pintype "passive"))
    )
    (net (code "83") (name "unconnected-(U26-PA14{slash}PGMD6-PadK6)") (class "Default")
      (node (ref "U26") (pin "K6") (pinfunction "PA14/PGMD6_K6") (pintype "passive"))
    )
    (net (code "84") (name "unconnected-(U26-PA16{slash}PGMD8-PadJ6)") (class "Default")
      (node (ref "U26") (pin "J6") (pinfunction "PA16/PGMD8_J6") (pintype "passive"))
    )
    (net (code "85") (name "unconnected-(U26-PA19{slash}PGMD11-PadJ7)") (class "Default")
      (node (ref "U26") (pin "J7") (pinfunction "PA19/PGMD11_J7") (pintype "passive"))
    )
    (net (code "86") (name "unconnected-(U26-PA27-PadH3)") (class "Default")
      (node (ref "U26") (pin "H3") (pinfunction "PA27_H3") (pintype "passive"))
    )
    (net (code "87") (name "unconnected-(U26-PA30-PadJ4)") (class "Default")
      (node (ref "U26") (pin "J4") (pinfunction "PA30_J4") (pintype "passive"))
    )
    (net (code "88") (name "unconnected-(U26-PA31-PadF4)") (class "Default")
      (node (ref "U26") (pin "F4") (pinfunction "PA31_F4") (pintype "passive"))
    )
    (net (code "89") (name "unconnected-(U26-PB0-PadG3)") (class "Default")
      (node (ref "U26") (pin "G3") (pinfunction "PB0_G3") (pintype "passive"))
    )
    (net (code "90") (name "unconnected-(U26-PB1-PadF1)") (class "Default")
      (node (ref "U26") (pin "F1") (pinfunction "PB1_F1") (pintype "passive"))
    )
    (net (code "91") (name "unconnected-(U26-PB2-PadG2)") (class "Default")
      (node (ref "U26") (pin "G2") (pinfunction "PB2_G2") (pintype "passive"))
    )
    (net (code "92") (name "unconnected-(U26-PB3-PadJ5)") (class "Default")
      (node (ref "U26") (pin "J5") (pinfunction "PB3_J5") (pintype "passive"))
    )
    (net (code "93") (name "unconnected-(U26-PB4-PadK5)") (class "Default")
      (node (ref "U26") (pin "K5") (pinfunction "PB4_K5") (pintype "passive"))
    )
    (net (code "94") (name "unconnected-(U26-PB5-PadH2)") (class "Default")
      (node (ref "U26") (pin "H2") (pinfunction "PB5_H2") (pintype "passive"))
    )
    (net (code "95") (name "unconnected-(U26-PB6-PadJ1)") (class "Default")
      (node (ref "U26") (pin "J1") (pinfunction "PB6_J1") (pintype "passive"))
    )
    (net (code "96") (name "unconnected-(U26-PB8-PadJ2)") (class "Default")
      (node (ref "U26") (pin "J2") (pinfunction "PB8_J2") (pintype "passive"))
    )
    (net (code "97") (name "unconnected-(U26-PB9-PadE4)") (class "Default")
      (node (ref "U26") (pin "E4") (pinfunction "PB9_E4") (pintype "passive"))
    )
    (net (code "98") (name "unconnected-(U26-PB10-PadB4)") (class "Default")
      (node (ref "U26") (pin "B4") (pinfunction "PB10_B4") (pintype "passive"))
    )
    (net (code "99") (name "unconnected-(U26-PB11-PadG1)") (class "Default")
      (node (ref "U26") (pin "G1") (pinfunction "PB11_G1") (pintype "passive"))
    )
    (net (code "100") (name "unconnected-(U26-PB12-PadF2)") (class "Default")
      (node (ref "U26") (pin "F2") (pinfunction "PB12_F2") (pintype "passive"))
    )
    (net (code "101") (name "unconnected-(U26-PB13-PadG4)") (class "Default")
      (node (ref "U26") (pin "G4") (pinfunction "PB13_G4") (pintype "passive"))
    )
    (net (code "102") (name "unconnected-(U26-PB14-PadC4)") (class "Default")
      (node (ref "U26") (pin "C4") (pinfunction "PB14_C4") (pintype "passive"))
    )
    (net (code "103") (name "unconnected-(U26-PB15-PadG7)") (class "Default")
      (node (ref "U26") (pin "G7") (pinfunction "PB15_G7") (pintype "passive"))
    )
    (net (code "104") (name "unconnected-(U26-PB16-PadF7)") (class "Default")
      (node (ref "U26") (pin "F7") (pinfunction "PB16_F7") (pintype "passive"))
    )
    (net (code "105") (name "unconnected-(U26-PB17-PadA4)") (class "Default")
      (node (ref "U26") (pin "A4") (pinfunction "PB17_A4") (pintype "passive"))
    )
    (net (code "106") (name "unconnected-(U26-PB18-PadB5)") (class "Default")
      (node (ref "U26") (pin "B5") (pinfunction "PB18_B5") (pintype "passive"))
    )
    (net (code "107") (name "unconnected-(U26-PB19-PadC5)") (class "Default")
      (node (ref "U26") (pin "C5") (pinfunction "PB19_C5") (pintype "passive"))
    )
    (net (code "108") (name "unconnected-(U26-PB20-PadD5)") (class "Default")
      (node (ref "U26") (pin "D5") (pinfunction "PB20_D5") (pintype "passive"))
    )
    (net (code "109") (name "unconnected-(U26-PB21-PadA5)") (class "Default")
      (node (ref "U26") (pin "A5") (pinfunction "PB21_A5") (pintype "passive"))
    )
    (net (code "110") (name "unconnected-(U26-PB22-PadC6)") (class "Default")
      (node (ref "U26") (pin "C6") (pinfunction "PB22_C6") (pintype "passive"))
    )
    (net (code "111") (name "unconnected-(U26-PB23-PadA6)") (class "Default")
      (node (ref "U26") (pin "A6") (pinfunction "PB23_A6") (pintype "passive"))
    )
    (net (code "112") (name "unconnected-(U26-PB24-PadB6)") (class "Default")
      (node (ref "U26") (pin "B6") (pinfunction "PB24_B6") (pintype "passive"))
    )
    (net (code "113") (name "unconnected-(U26-TEST-PadD7)") (class "Default")
      (node (ref "U26") (pin "D7") (pinfunction "TEST_D7") (pintype "passive"))
    )
    (net (code "114") (name "unconnected-(U26-XIN32-PadA10)") (class "Default")
      (node (ref "U26") (pin "A10") (pinfunction "XIN32_A10") (pintype "passive"))
    )
    (net (code "115") (name "unconnected-(U26-XOUT-PadA3)") (class "Default")
      (node (ref "U26") (pin "A3") (pinfunction "XOUT_A3") (pintype "passive+no_connect"))
    )
    (net (code "116") (name "unconnected-(U26-XOUT32-PadB10)") (class "Default")
      (node (ref "U26") (pin "B10") (pinfunction "XOUT32_B10") (pintype "passive"))
    )
    (net (code "117") (name "unconnected-(U27-YC-Pad9)") (class "Default")
      (node (ref "U27") (pin "9") (pinfunction "YC_9") (pintype "passive+no_connect"))
    )
    (net (code "118") (name "unconnected-(U27-YD-Pad12)") (class "Default")
      (node (ref "U27") (pin "12") (pinfunction "YD_12") (pintype "passive+no_connect"))
    )
    (net (code "119") (name "unconnected-(U28-NC-Pad5)") (class "Default")
      (node (ref "U28") (pin "5") (pinfunction "NC_5") (pintype "passive+no_connect"))
    )
    (net (code "120") (name "unconnected-(Y10-~{STB}-Pad1)") (class "Default")
      (node (ref "Y10") (pin "1") (pinfunction "~{STB}_1") (pintype "input+no_connect"))
    )
  )
)
